# NaviMecBoard.net
KiCad netlist of a schematic drawn in EAGLE
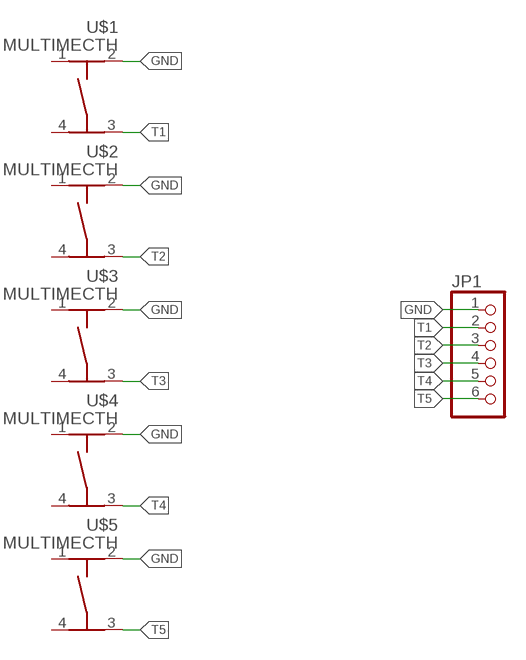
[diagram p0: schematic, sheet 1]

(export (version "E")
  (design (tool "Eeschema 10.0.6"))
  (components
    (comp (ref "JP1")
      (value "PINHD-1X6")
      (footprint "eagle-import:1X06")
      (libsource (lib "eagle-import") (part "PINHD-1X6"))
    )
    (comp (ref "U$1")
      (value "MULTIMECTH")
      (footprint "eagle-import:MULTIMEC_TH")
      (libsource (lib "eagle-import") (part "MULTIMECTH"))
    )
    (comp (ref "U$2")
      (value "MULTIMECTH")
      (footprint "eagle-import:MULTIMEC_TH")
      (libsource (lib "eagle-import") (part "MULTIMECTH"))
    )
    (comp (ref "U$3")
      (value "MULTIMECTH")
      (footprint "eagle-import:MULTIMEC_TH")
      (libsource (lib "eagle-import") (part "MULTIMECTH"))
    )
    (comp (ref "U$4")
      (value "MULTIMECTH")
      (footprint "eagle-import:MULTIMEC_TH")
      (libsource (lib "eagle-import") (part "MULTIMECTH"))
    )
    (comp (ref "U$5")
      (value "MULTIMECTH")
      (footprint "eagle-import:MULTIMEC_TH")
      (libsource (lib "eagle-import") (part "MULTIMECTH"))
    )
  )
  (nets
    (net (code "1") (name "GND") (class "Default")
      (node (ref "JP1") (pin "1") (pinfunction "1_1") (pintype "passive"))
      (node (ref "U$1") (pin "2") (pinfunction "2_2") (pintype "passive"))
      (node (ref "U$2") (pin "2") (pinfunction "2_2") (pintype "passive"))
      (node (ref "U$3") (pin "2") (pinfunction "2_2") (pintype "passive"))
      (node (ref "U$4") (pin "2") (pinfunction "2_2") (pintype "passive"))
      (node (ref "U$5") (pin "2") (pinfunction "2_2") (pintype "passive"))
    )
    (net (code "2") (name "T1") (class "Default")
      (node (ref "JP1") (pin "2") (pinfunction "2_2") (pintype "passive"))
      (node (ref "U$1") (pin "3") (pinfunction "4_3") (pintype "passive"))
    )
    (net (code "3") (name "T2") (class "Default")
      (node (ref "JP1") (pin "3") (pinfunction "3_3") (pintype "passive"))
      (node (ref "U$2") (pin "3") (pinfunction "4_3") (pintype "passive"))
    )
    (net (code "4") (name "T3") (class "Default")
      (node (ref "JP1") (pin "4") (pinfunction "4_4") (pintype "passive"))
      (node (ref "U$3") (pin "3") (pinfunction "4_3") (pintype "passive"))
    )
    (net (code "5") (name "T4") (class "Default")
      (node (ref "JP1") (pin "5") (pinfunction "5_5") (pintype "passive"))
      (node (ref "U$4") (pin "3") (pinfunction "4_3") (pintype "passive"))
    )
    (net (code "6") (name "T5") (class "Default")
      (node (ref "JP1") (pin "6") (pinfunction "6_6") (pintype "passive"))
      (node (ref "U$5") (pin "3") (pinfunction "4_3") (pintype "passive"))
    )
    (net (code "7") (name "unconnected-(U$1-3-Pad4)") (class "Default")
      (node (ref "U$1") (pin "4") (pinfunction "3_4") (pintype "passive"))
    )
    (net (code "8") (name "unconnected-(U$1-Pad1)") (class "Default")
      (node (ref "U$1") (pin "1") (pinfunction "1_1") (pintype "passive"))
    )
    (net (code "9") (name "unconnected-(U$2-3-Pad4)") (class "Default")
      (node (ref "U$2") (pin "4") (pinfunction "3_4") (pintype "passive"))
    )
    (net (code "10") (name "unconnected-(U$2-Pad1)") (class "Default")
      (node (ref "U$2") (pin "1") (pinfunction "1_1") (pintype "passive"))
    )
    (net (code "11") (name "unconnected-(U$3-3-Pad4)") (class "Default")
      (node (ref "U$3") (pin "4") (pinfunction "3_4") (pintype "passive"))
    )
    (net (code "12") (name "unconnected-(U$3-Pad1)") (class "Default")
      (node (ref "U$3") (pin "1") (pinfunction "1_1") (pintype "passive"))
    )
    (net (code "13") (name "unconnected-(U$4-3-Pad4)") (class "Default")
      (node (ref "U$4") (pin "4") (pinfunction "3_4") (pintype "passive"))
    )
    (net (code "14") (name "unconnected-(U$4-Pad1)") (class "Default")
      (node (ref "U$4") (pin "1") (pinfunction "1_1") (pintype "passive"))
    )
    (net (code "15") (name "unconnected-(U$5-3-Pad4)") (class "Default")
      (node (ref "U$5") (pin "4") (pinfunction "3_4") (pintype "passive"))
    )
    (net (code "16") (name "unconnected-(U$5-Pad1)") (class "Default")
      (node (ref "U$5") (pin "1") (pinfunction "1_1") (pintype "passive"))
    )
  )
)
